# modFOC-Debug.net
KiCad netlist of a schematic drawn in Altium Designer
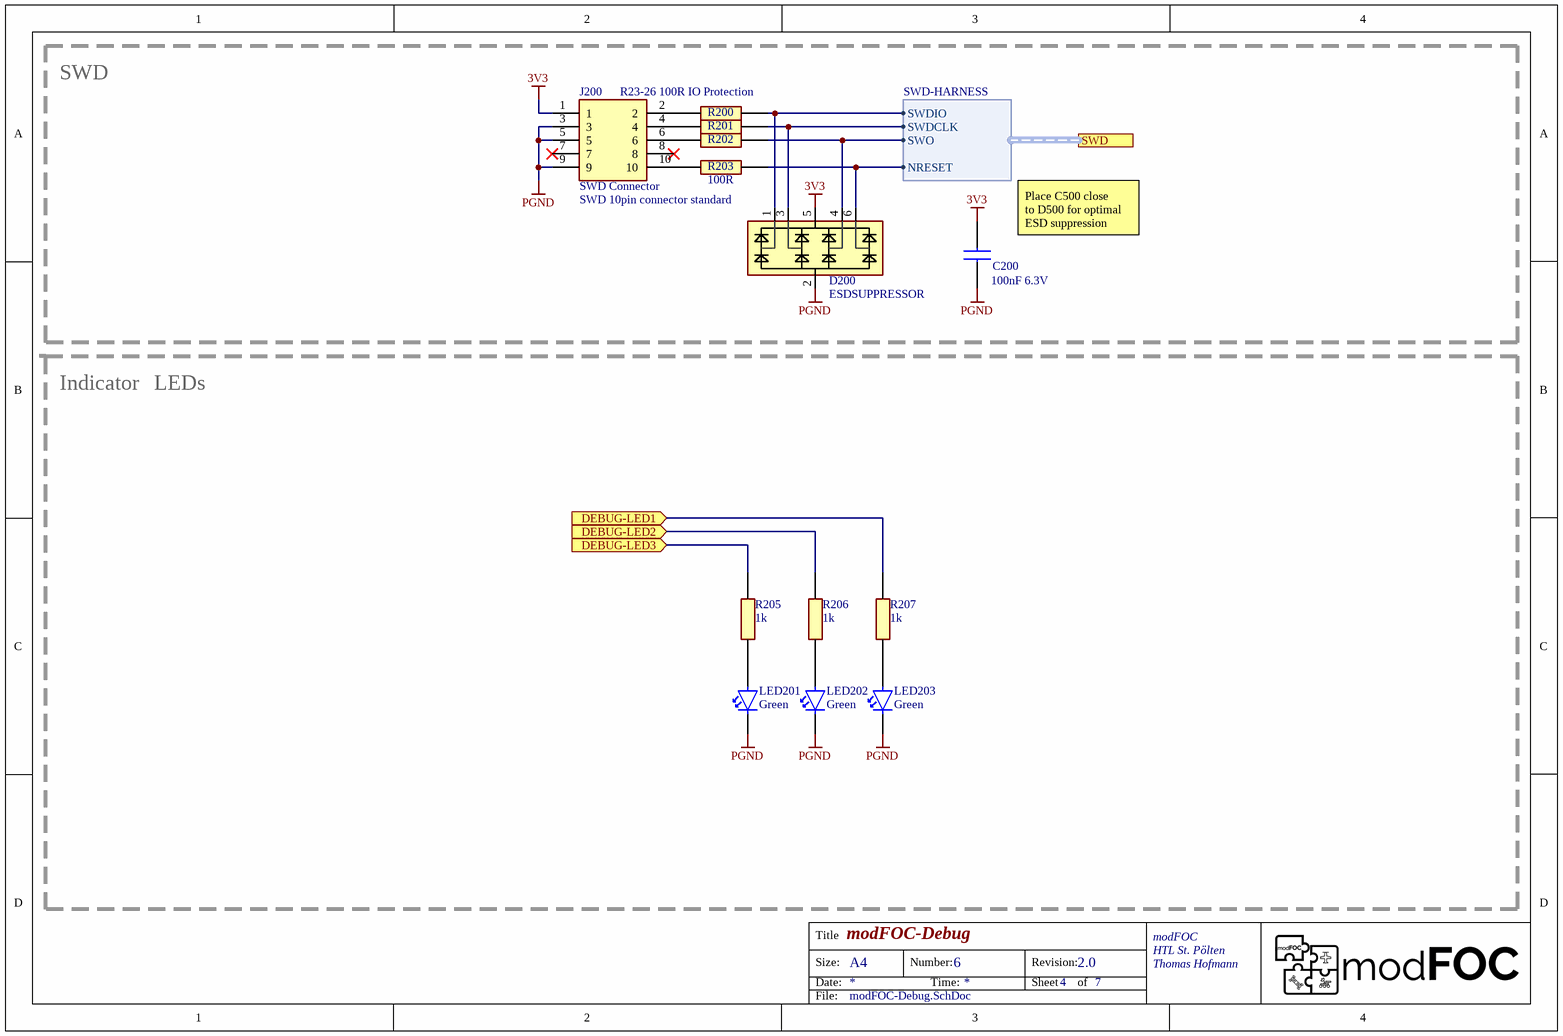
[diagram p0: modFOC-Debug.SchDoc]

(export (version "E")
  (design (tool "Eeschema 10.0.6"))
  (components
    (comp (ref "C200")
      (value "100nF 6.3V")
      (footprint "CAPC1608X97N")
      (description "Capacitor")
      (libsource (lib "RcMPPTLib") (part "C0603"))
    )
    (comp (ref "D200")
      (value "ESDSUPPRESSOR")
      (footprint "SOT23-6")
      (description "TVS Diode Array")
      (libsource (lib "RcMPPTLib") (part "ESDSUPPRESSOR"))
    )
    (comp (ref "J200")
      (value "SWD Connector")
      (footprint "HUSSP10W40P127_2X5_635X340X420P")
      (description "Connector")
      (fields
        (field (name "MANUFACTURER_PART_NUMBER") "M50-3600542R")
        (field (name "MOUSER PART NUMBER") "855-M50-3600542R")
      )
      (libsource (lib "RcMPPTLib") (part "M50-3600542R"))
    )
    (comp (ref "LED201")
      (value "Green")
      (footprint "CHIPLED_0603")
      (description "LED")
      (libsource (lib "RcMPPTLib") (part "CHIPLED0603"))
    )
    (comp (ref "LED202")
      (value "Green")
      (footprint "CHIPLED_0603")
      (description "LED")
      (libsource (lib "RcMPPTLib") (part "CHIPLED0603"))
    )
    (comp (ref "LED203")
      (value "Green")
      (footprint "CHIPLED_0603")
      (description "LED")
      (libsource (lib "RcMPPTLib") (part "CHIPLED0603"))
    )
    (comp (ref "R200")
      (value "100R")
      (footprint "RESC1005X40N")
      (description "Resistor")
      (libsource (lib "RcMPPTLib") (part "R0402"))
    )
    (comp (ref "R201")
      (value "100R")
      (footprint "RESC1005X40N")
      (description "Resistor")
      (libsource (lib "RcMPPTLib") (part "R0402"))
    )
    (comp (ref "R202")
      (value "100R")
      (footprint "RESC1005X40N")
      (description "Resistor")
      (libsource (lib "RcMPPTLib") (part "R0402"))
    )
    (comp (ref "R203")
      (value "100R")
      (footprint "RESC1005X40N")
      (description "Resistor")
      (libsource (lib "RcMPPTLib") (part "R0402"))
    )
    (comp (ref "R205")
      (value "1k")
      (footprint "RESC1608X50N")
      (description "Resistor")
      (libsource (lib "RcMPPTLib") (part "R0603"))
    )
    (comp (ref "R206")
      (value "1k")
      (footprint "RESC1608X50N")
      (description "Resistor")
      (libsource (lib "RcMPPTLib") (part "R0603"))
    )
    (comp (ref "R207")
      (value "1k")
      (footprint "RESC1608X50N")
      (description "Resistor")
      (libsource (lib "RcMPPTLib") (part "R0603"))
    )
  )
  (nets
    (net (code "2") (name "/DEBUG-LED1") (class "Default")
      (node (ref "R207") (pin "1") (pinfunction "1_1") (pintype "passive"))
    )
    (net (code "3") (name "/DEBUG-LED2") (class "Default")
      (node (ref "R206") (pin "1") (pinfunction "1_1") (pintype "passive"))
    )
    (net (code "4") (name "/DEBUG-LED3") (class "Default")
      (node (ref "R205") (pin "1") (pinfunction "1_1") (pintype "passive"))
    )
    (net (code "6") (name "3V3") (class "Default")
      (node (ref "C200") (pin "2") (pinfunction "2_2") (pintype "passive"))
      (node (ref "D200") (pin "5") (pinfunction "VDD_5") (pintype "passive"))
      (node (ref "J200") (pin "1") (pinfunction "1_1") (pintype "passive"))
    )
    (net (code "7") (name "Net-(D200-CH1)") (class "Default")
      (node (ref "D200") (pin "1") (pinfunction "CH1_1") (pintype "passive"))
      (node (ref "R200") (pin "2") (pinfunction "2_2") (pintype "passive"))
    )
    (net (code "8") (name "Net-(D200-CH2)") (class "Default")
      (node (ref "D200") (pin "3") (pinfunction "CH2_3") (pintype "passive"))
      (node (ref "R201") (pin "2") (pinfunction "2_2") (pintype "passive"))
    )
    (net (code "9") (name "Net-(D200-CH3)") (class "Default")
      (node (ref "D200") (pin "4") (pinfunction "CH3_4") (pintype "passive"))
      (node (ref "R202") (pin "2") (pinfunction "2_2") (pintype "passive"))
    )
    (net (code "10") (name "Net-(D200-CH4)") (class "Default")
      (node (ref "D200") (pin "6") (pinfunction "CH4_6") (pintype "passive"))
      (node (ref "R203") (pin "2") (pinfunction "2_2") (pintype "passive"))
    )
    (net (code "11") (name "Net-(J200-Pad2)") (class "Default")
      (node (ref "J200") (pin "2") (pinfunction "2_2") (pintype "passive"))
      (node (ref "R200") (pin "1") (pinfunction "1_1") (pintype "passive"))
    )
    (net (code "12") (name "Net-(J200-Pad4)") (class "Default")
      (node (ref "J200") (pin "4") (pinfunction "4_4") (pintype "passive"))
      (node (ref "R201") (pin "1") (pinfunction "1_1") (pintype "passive"))
    )
    (net (code "13") (name "Net-(J200-Pad6)") (class "Default")
      (node (ref "J200") (pin "6") (pinfunction "6_6") (pintype "passive"))
      (node (ref "R202") (pin "1") (pinfunction "1_1") (pintype "passive"))
    )
    (net (code "14") (name "Net-(J200-Pad10)") (class "Default")
      (node (ref "J200") (pin "10") (pinfunction "10_10") (pintype "passive"))
      (node (ref "R203") (pin "1") (pinfunction "1_1") (pintype "passive"))
    )
    (net (code "15") (name "Net-(LED201-A)") (class "Default")
      (node (ref "LED201") (pin "2") (pinfunction "A_2") (pintype "passive"))
      (node (ref "R205") (pin "2") (pinfunction "2_2") (pintype "passive"))
    )
    (net (code "16") (name "Net-(LED202-A)") (class "Default")
      (node (ref "LED202") (pin "2") (pinfunction "A_2") (pintype "passive"))
      (node (ref "R206") (pin "2") (pinfunction "2_2") (pintype "passive"))
    )
    (net (code "17") (name "Net-(LED203-A)") (class "Default")
      (node (ref "LED203") (pin "2") (pinfunction "A_2") (pintype "passive"))
      (node (ref "R207") (pin "2") (pinfunction "2_2") (pintype "passive"))
    )
    (net (code "18") (name "PGND") (class "Default")
      (node (ref "C200") (pin "1") (pinfunction "1_1") (pintype "passive"))
      (node (ref "D200") (pin "2") (pinfunction "GND_2") (pintype "passive"))
      (node (ref "J200") (pin "3") (pinfunction "3_3") (pintype "passive"))
      (node (ref "J200") (pin "5") (pinfunction "5_5") (pintype "passive"))
      (node (ref "J200") (pin "9") (pinfunction "9_9") (pintype "passive"))
      (node (ref "LED201") (pin "1") (pinfunction "K_1") (pintype "passive"))
      (node (ref "LED202") (pin "1") (pinfunction "K_1") (pintype "passive"))
      (node (ref "LED203") (pin "1") (pinfunction "K_1") (pintype "passive"))
    )
    (net (code "19") (name "unconnected-(J200-Pad7)") (class "Default")
      (node (ref "J200") (pin "7") (pinfunction "7_7") (pintype "passive+no_connect"))
    )
    (net (code "20") (name "unconnected-(J200-Pad8)") (class "Default")
      (node (ref "J200") (pin "8") (pinfunction "8_8") (pintype "passive+no_connect"))
    )
  )
)
